# team13_4.net
KiCad netlist of a schematic drawn in EAGLE
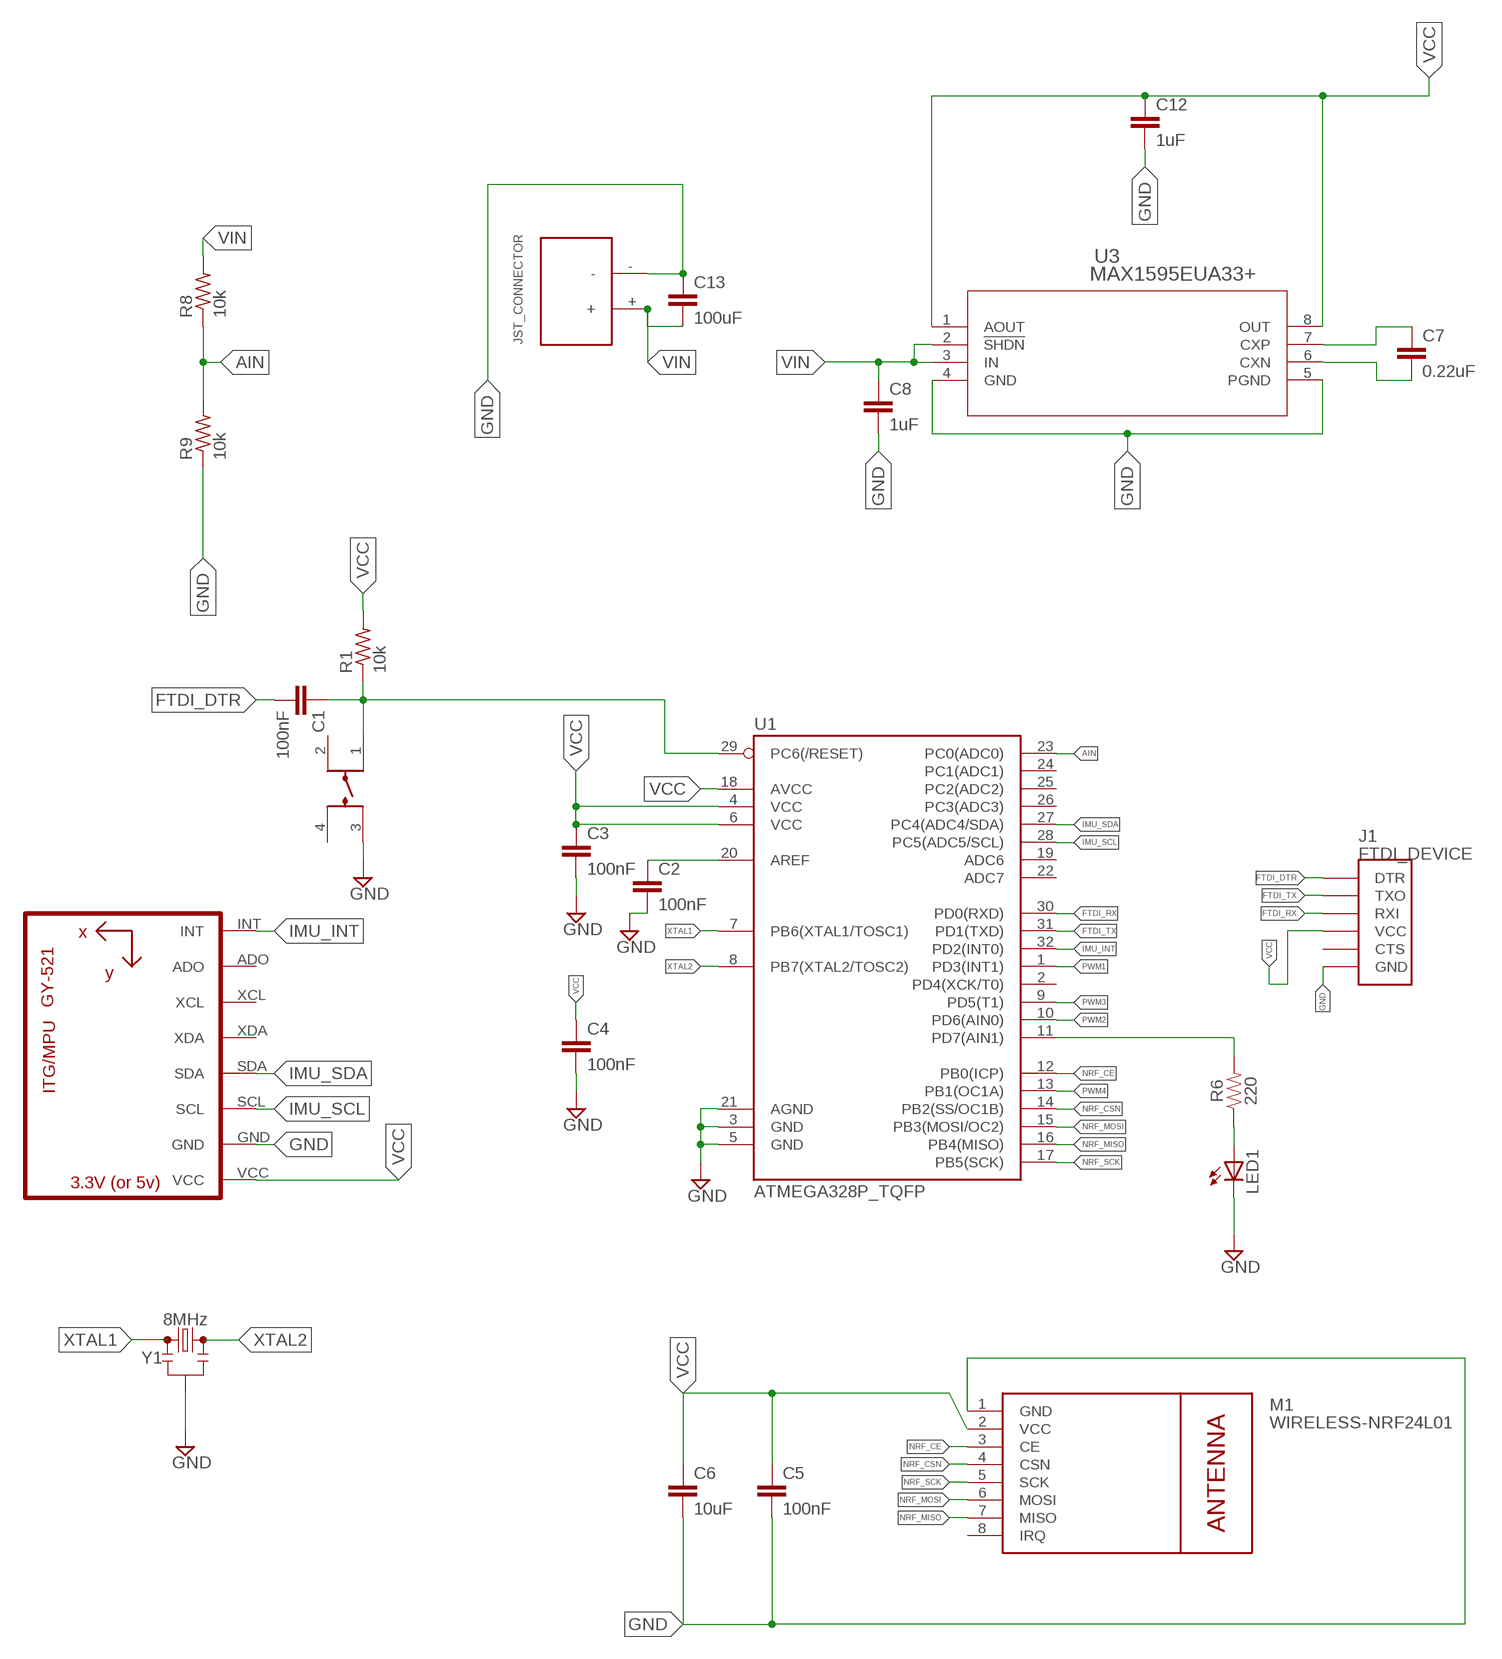
[diagram p0: schematic, sheet 1, part 1 of 3]
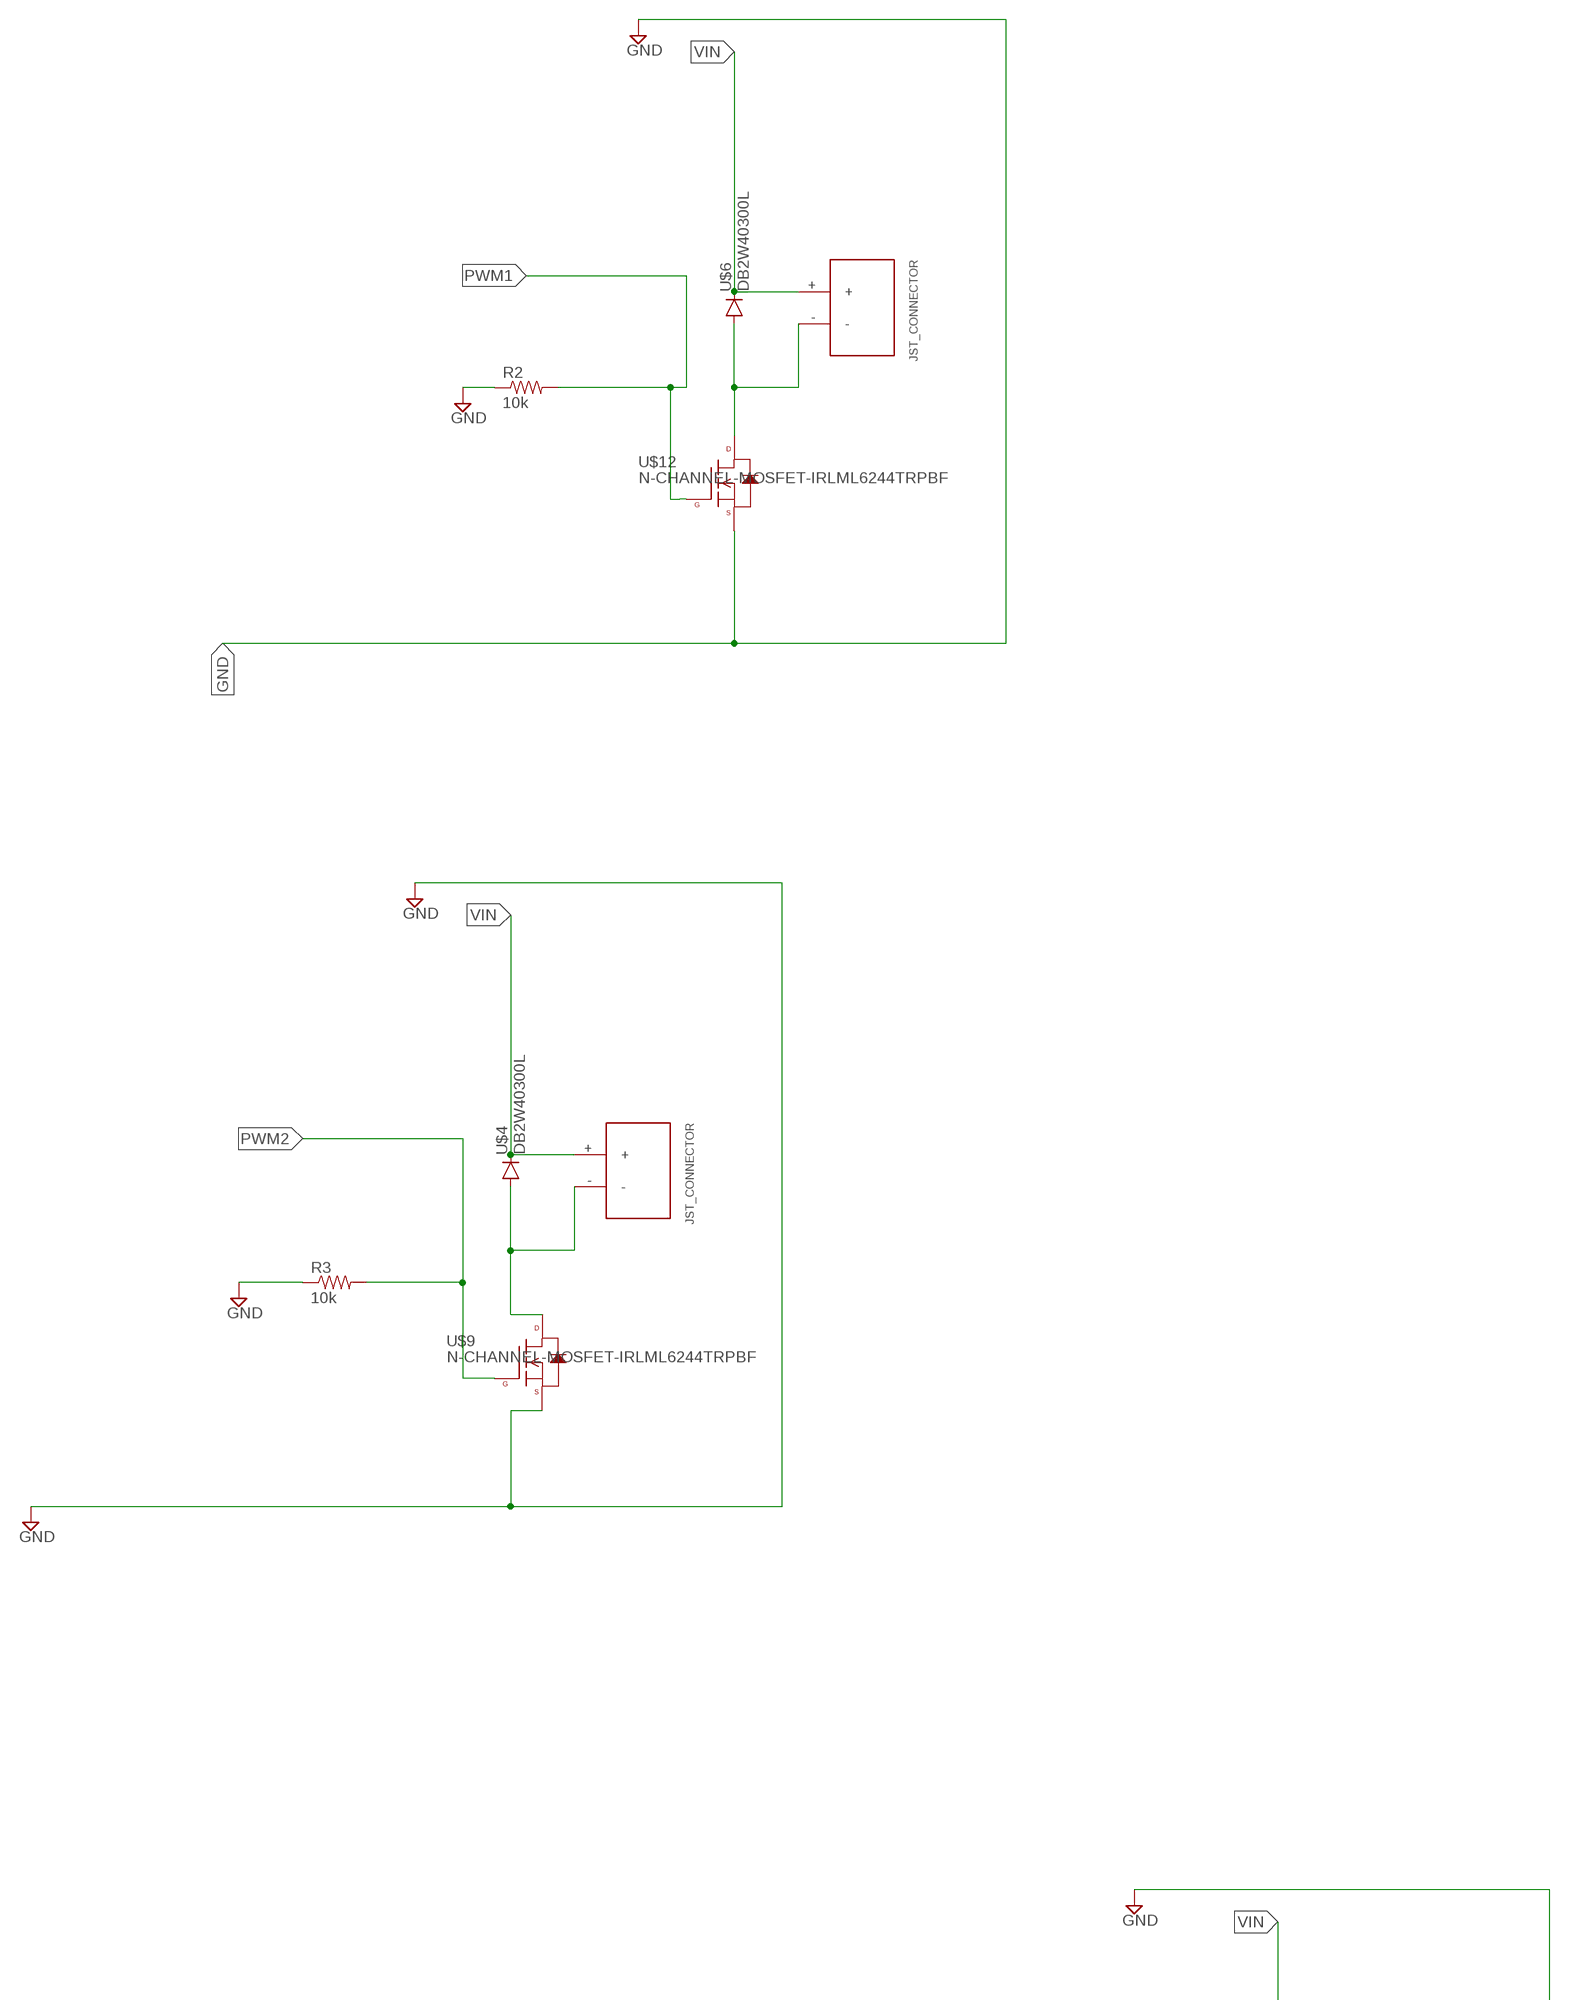
[diagram p1: schematic, sheet 1, part 2 of 3]
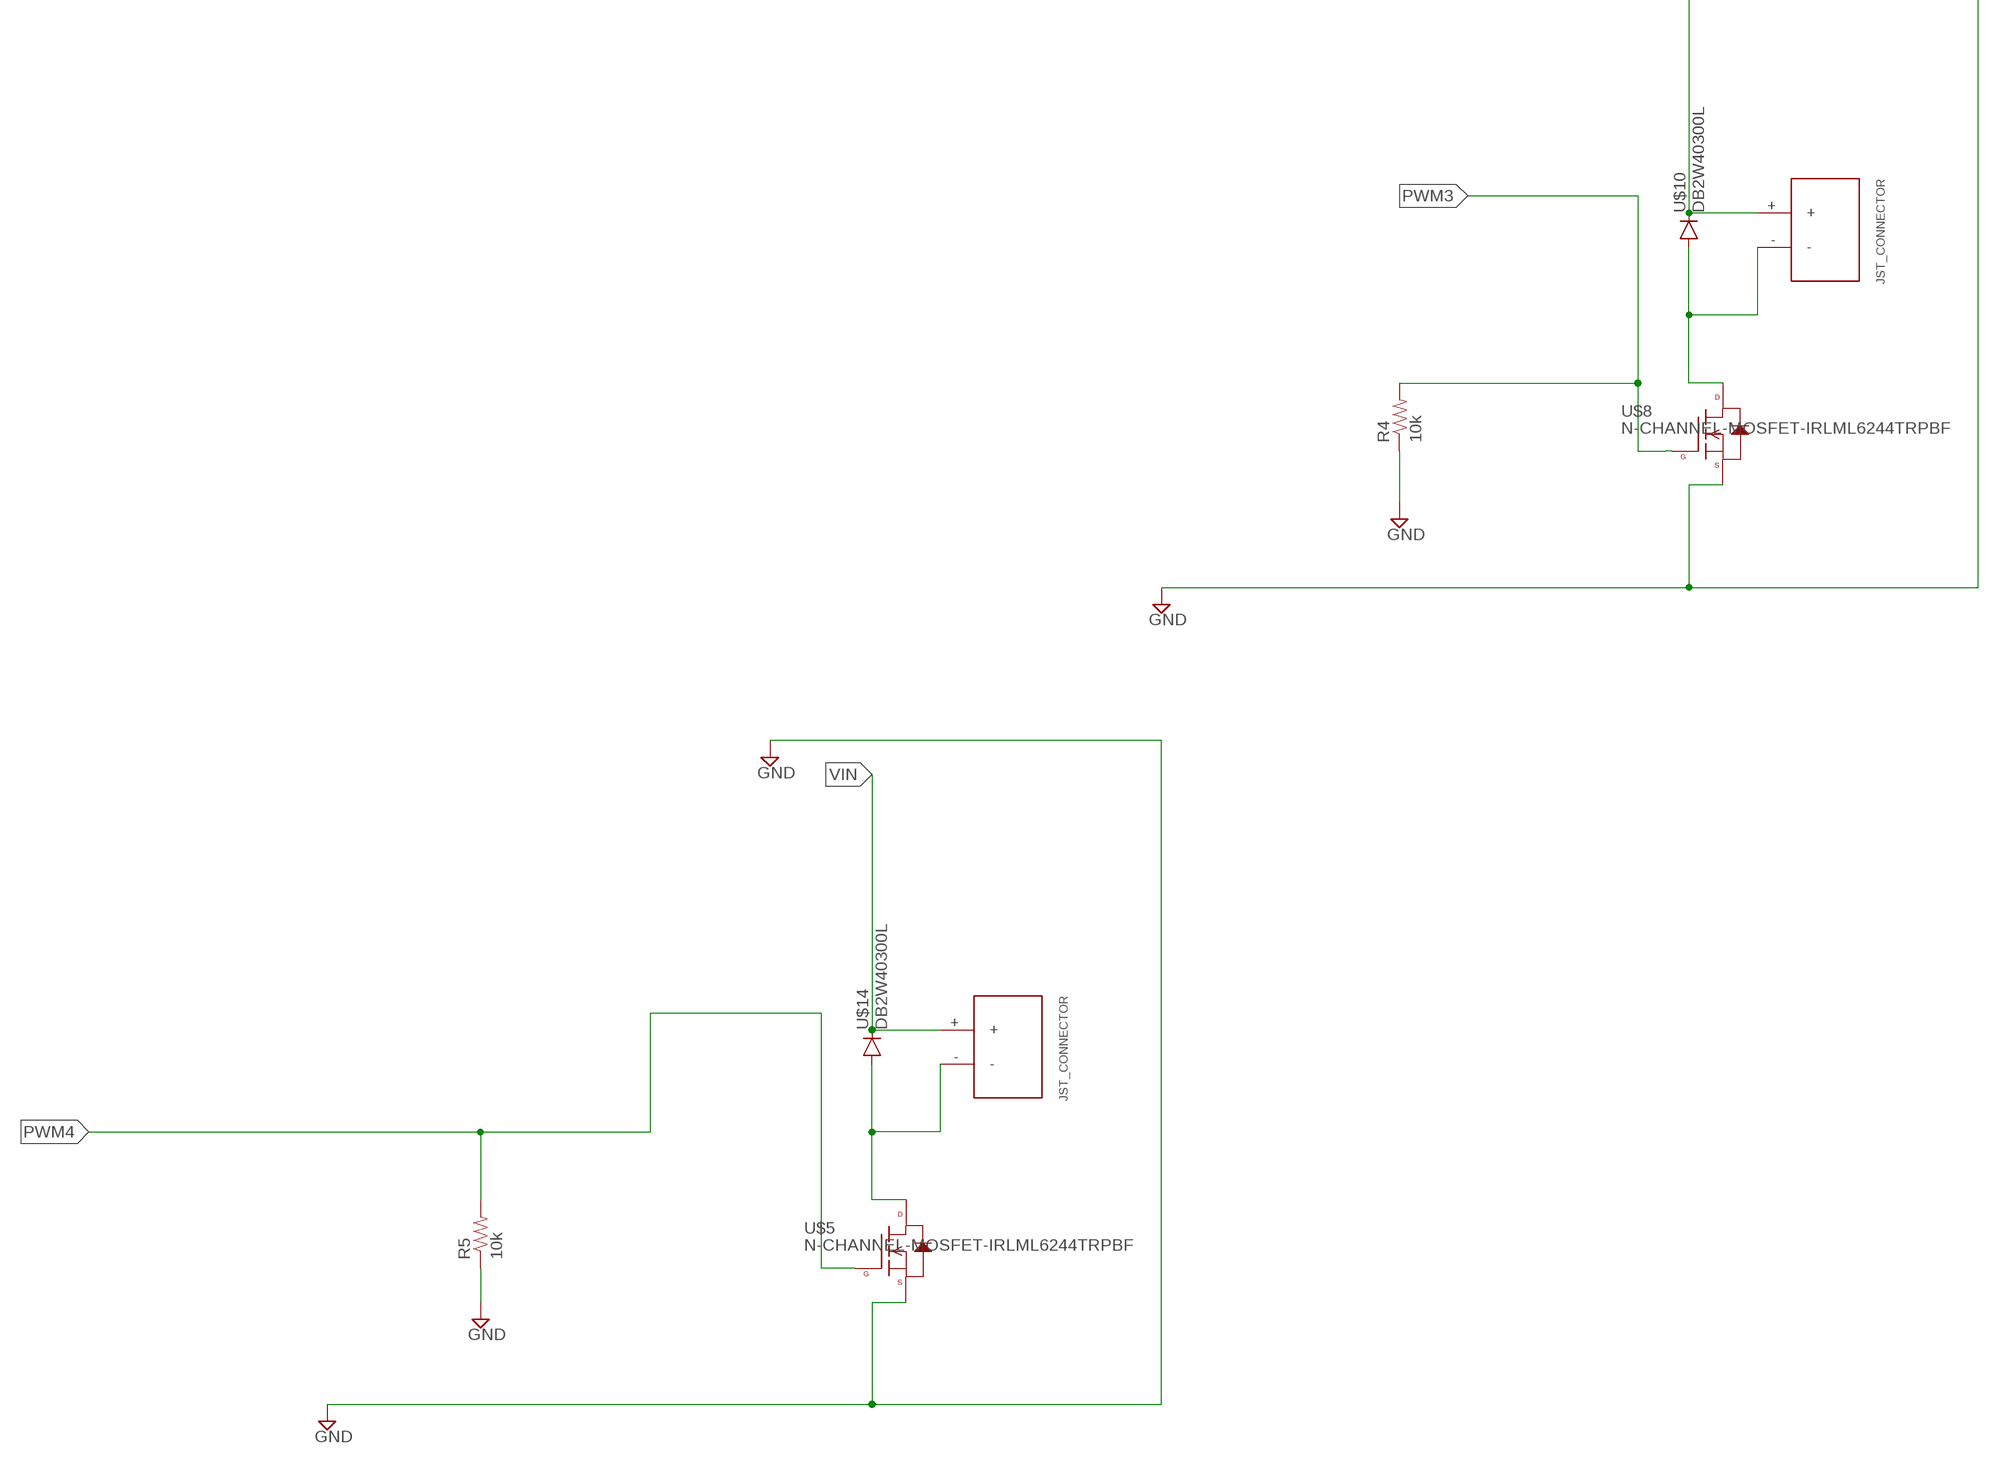
[diagram p2: schematic, sheet 1, part 3 of 3]

(export (version "E")
  (design (tool "Eeschema 10.0.6"))
  (components
    (comp (ref "C1")
      (value "100nF")
      (footprint "eagle-import:C0603")
      (libsource (lib "eagle-import") (part "C-EUC0603"))
    )
    (comp (ref "C2")
      (value "100nF")
      (footprint "eagle-import:C0603")
      (libsource (lib "eagle-import") (part "C-EUC0603"))
    )
    (comp (ref "C3")
      (value "100nF")
      (footprint "eagle-import:C0603")
      (libsource (lib "eagle-import") (part "C-EUC0603"))
    )
    (comp (ref "C4")
      (value "100nF")
      (footprint "eagle-import:C0603")
      (libsource (lib "eagle-import") (part "C-EUC0603"))
    )
    (comp (ref "C5")
      (value "100nF")
      (footprint "eagle-import:C0603")
      (libsource (lib "eagle-import") (part "C-EUC0603"))
    )
    (comp (ref "C6")
      (value "10uF")
      (footprint "eagle-import:C0603")
      (libsource (lib "eagle-import") (part "C-EUC0603"))
    )
    (comp (ref "C7")
      (value "0.22uF")
      (footprint "eagle-import:C0603")
      (libsource (lib "eagle-import") (part "C-EUC0603"))
    )
    (comp (ref "C8")
      (value "1uF")
      (footprint "eagle-import:C0805")
      (libsource (lib "eagle-import") (part "C-EUC0805"))
    )
    (comp (ref "C12")
      (value "1uF")
      (footprint "eagle-import:C0805")
      (libsource (lib "eagle-import") (part "C-EUC0805"))
    )
    (comp (ref "C13")
      (value "100uF")
      (footprint "eagle-import:C1210")
      (libsource (lib "eagle-import") (part "C-EUC1210"))
    )
    (comp (ref "J1")
      (value "FTDI_DEVICE")
      (footprint "eagle-import:FTDI_DEVICE_SIDE")
      (libsource (lib "eagle-import") (part "FTDI_DEVICE"))
    )
    (comp (ref "LED1")
      (value "LED1206")
      (footprint "eagle-import:LED-1206")
      (libsource (lib "eagle-import") (part "LED1206"))
    )
    (comp (ref "M1")
      (value "WIRELESS-NRF24L01")
      (footprint "eagle-import:WIRELESS-NRF24L01")
      (libsource (lib "eagle-import") (part "WIRELESS-NRF24L01"))
    )
    (comp (ref "R1")
      (value "10k")
      (footprint "eagle-import:R0603")
      (libsource (lib "eagle-import") (part "R-US_R0603"))
    )
    (comp (ref "R2")
      (value "10k")
      (footprint "eagle-import:0603-RES")
      (libsource (lib "eagle-import") (part "RESISTOR0603"))
    )
    (comp (ref "R3")
      (value "10k")
      (footprint "eagle-import:0603-RES")
      (libsource (lib "eagle-import") (part "RESISTOR0603"))
    )
    (comp (ref "R4")
      (value "10k")
      (footprint "eagle-import:0603-RES")
      (libsource (lib "eagle-import") (part "RESISTOR0603"))
    )
    (comp (ref "R5")
      (value "10k")
      (footprint "eagle-import:0603-RES")
      (libsource (lib "eagle-import") (part "RESISTOR0603"))
    )
    (comp (ref "R6")
      (value "220")
      (footprint "eagle-import:0603")
      (libsource (lib "eagle-import") (part "220OHM-0603-1/10W-1%"))
    )
    (comp (ref "R8")
      (value "10k")
      (footprint "eagle-import:R0603")
      (libsource (lib "eagle-import") (part "R-US_R0603"))
    )
    (comp (ref "R9")
      (value "10k")
      (footprint "eagle-import:R0603")
      (libsource (lib "eagle-import") (part "R-US_R0603"))
    )
    (comp (ref "U$1")
      (value "LL3301NF065QG")
      (footprint "eagle-import:LL3301NF065QG")
      (libsource (lib "eagle-import") (part "LL3301NF065QG"))
    )
    (comp (ref "U$3")
      (value "JST_CONNECTOR_FEMALE")
      (footprint "eagle-import:JST_CONNECTOR_FEMALE")
      (libsource (lib "eagle-import") (part "JST_CONNECTOR_FEMALE"))
    )
    (comp (ref "U$4")
      (value "DB2W40300L")
      (footprint "eagle-import:MINI2-F3-B")
      (libsource (lib "eagle-import") (part "DB2W40300L"))
    )
    (comp (ref "U$5")
      (value "N-CHANNEL-MOSFET-IRLML6244TRPBF")
      (footprint "eagle-import:SOT23-3")
      (libsource (lib "eagle-import") (part "N-CHANNEL-MOSFET-IRLML6244TRPBF"))
    )
    (comp (ref "U$6")
      (value "DB2W40300L")
      (footprint "eagle-import:MINI2-F3-B")
      (libsource (lib "eagle-import") (part "DB2W40300L"))
    )
    (comp (ref "U$7")
      (value "JST_CONNECTOR_FEMALE")
      (footprint "eagle-import:JST_CONNECTOR_FEMALE")
      (libsource (lib "eagle-import") (part "JST_CONNECTOR_FEMALE"))
    )
    (comp (ref "U$8")
      (value "N-CHANNEL-MOSFET-IRLML6244TRPBF")
      (footprint "eagle-import:SOT23-3")
      (libsource (lib "eagle-import") (part "N-CHANNEL-MOSFET-IRLML6244TRPBF"))
    )
    (comp (ref "U$9")
      (value "N-CHANNEL-MOSFET-IRLML6244TRPBF")
      (footprint "eagle-import:SOT23-3")
      (libsource (lib "eagle-import") (part "N-CHANNEL-MOSFET-IRLML6244TRPBF"))
    )
    (comp (ref "U$10")
      (value "DB2W40300L")
      (footprint "eagle-import:MINI2-F3-B")
      (libsource (lib "eagle-import") (part "DB2W40300L"))
    )
    (comp (ref "U$11")
      (value "JST_CONNECTOR_FEMALE")
      (footprint "eagle-import:JST_CONNECTOR_FEMALE")
      (libsource (lib "eagle-import") (part "JST_CONNECTOR_FEMALE"))
    )
    (comp (ref "U$12")
      (value "N-CHANNEL-MOSFET-IRLML6244TRPBF")
      (footprint "eagle-import:SOT23-3")
      (libsource (lib "eagle-import") (part "N-CHANNEL-MOSFET-IRLML6244TRPBF"))
    )
    (comp (ref "U$14")
      (value "DB2W40300L")
      (footprint "eagle-import:MINI2-F3-B")
      (libsource (lib "eagle-import") (part "DB2W40300L"))
    )
    (comp (ref "U$15")
      (value "JST_CONNECTOR_FEMALE")
      (footprint "eagle-import:JST_CONNECTOR_FEMALE")
      (libsource (lib "eagle-import") (part "JST_CONNECTOR_FEMALE"))
    )
    (comp (ref "U$19")
      (value "JST_CONNECTOR_FEMALE")
      (footprint "eagle-import:JST_CONNECTOR_FEMALE")
      (libsource (lib "eagle-import") (part "JST_CONNECTOR_FEMALE"))
    )
    (comp (ref "U1")
      (value "ATMEGA328P_TQFP")
      (footprint "eagle-import:TQFP32-08")
      (libsource (lib "eagle-import") (part "ATMEGA328P_TQFP"))
    )
    (comp (ref "U2")
      (value "GY-521MPU6050")
      (footprint "eagle-import:GY-521")
      (libsource (lib "eagle-import") (part "GY-521MPU6050"))
    )
    (comp (ref "U3")
      (value "MAX1595EUA33+")
      (footprint "eagle-import:21-0036K")
      (libsource (lib "eagle-import") (part "MAX1595EUA33+"))
    )
    (comp (ref "Y1")
      (value "8MHz")
      (footprint "eagle-import:RESONATOR-SMD-3.2X1.3")
      (libsource (lib "eagle-import") (part "RESONATOR-8MHZSMD_3.2X1.3"))
    )
  )
  (nets
    (net (code "1") (name "AIN") (class "Default")
      (node (ref "R8") (pin "1") (pinfunction "1_1") (pintype "passive"))
      (node (ref "R9") (pin "2") (pinfunction "2_2") (pintype "passive"))
      (node (ref "U1") (pin "23") (pinfunction "PC0(ADC0)_23") (pintype "bidirectional"))
    )
    (net (code "2") (name "FTDI_DTR") (class "Default")
      (node (ref "C1") (pin "2") (pinfunction "2_2") (pintype "passive"))
      (node (ref "J1") (pin "P$1") (pinfunction "DTR_P$1") (pintype "bidirectional"))
    )
    (net (code "3") (name "FTDI_RX") (class "Default")
      (node (ref "J1") (pin "P$3") (pinfunction "RXI_P$3") (pintype "bidirectional"))
      (node (ref "U1") (pin "30") (pinfunction "PD0(RXD)_30") (pintype "bidirectional"))
    )
    (net (code "4") (name "FTDI_TX") (class "Default")
      (node (ref "J1") (pin "P$2") (pinfunction "TXO_P$2") (pintype "bidirectional"))
      (node (ref "U1") (pin "31") (pinfunction "PD1(TXD)_31") (pintype "bidirectional"))
    )
    (net (code "5") (name "GND") (class "Default")
      (node (ref "C12") (pin "2") (pinfunction "2_2") (pintype "passive"))
      (node (ref "C13") (pin "1") (pinfunction "1_1") (pintype "passive"))
      (node (ref "C2") (pin "2") (pinfunction "2_2") (pintype "passive"))
      (node (ref "C3") (pin "2") (pinfunction "2_2") (pintype "passive"))
      (node (ref "C4") (pin "2") (pinfunction "2_2") (pintype "passive"))
      (node (ref "C5") (pin "2") (pinfunction "2_2") (pintype "passive"))
      (node (ref "C6") (pin "2") (pinfunction "2_2") (pintype "passive"))
      (node (ref "C8") (pin "2") (pinfunction "2_2") (pintype "passive"))
      (node (ref "J1") (pin "P$6") (pinfunction "GND_P$6") (pintype "bidirectional"))
      (node (ref "LED1") (pin "C") (pinfunction "C_C") (pintype "passive"))
      (node (ref "M1") (pin "1") (pinfunction "GND_1") (pintype "power_in"))
      (node (ref "R2") (pin "1") (pinfunction "1_1") (pintype "passive"))
      (node (ref "R3") (pin "1") (pinfunction "1_1") (pintype "passive"))
      (node (ref "R4") (pin "1") (pinfunction "1_1") (pintype "passive"))
      (node (ref "R5") (pin "1") (pinfunction "1_1") (pintype "passive"))
      (node (ref "R9") (pin "1") (pinfunction "1_1") (pintype "passive"))
      (node (ref "U$1") (pin "3") (pinfunction "3_3") (pintype "passive"))
      (node (ref "U$12") (pin "2") (pinfunction "S_2") (pintype "passive"))
      (node (ref "U$19") (pin "-") (pinfunction "-_-") (pintype "bidirectional"))
      (node (ref "U$5") (pin "2") (pinfunction "S_2") (pintype "passive"))
      (node (ref "U$8") (pin "2") (pinfunction "S_2") (pintype "passive"))
      (node (ref "U$9") (pin "2") (pinfunction "S_2") (pintype "passive"))
      (node (ref "U1") (pin "21") (pinfunction "AGND_21") (pintype "bidirectional"))
      (node (ref "U1") (pin "3") (pinfunction "GND_3") (pintype "bidirectional"))
      (node (ref "U1") (pin "5") (pinfunction "GND_5") (pintype "bidirectional"))
      (node (ref "U2") (pin "GND") (pinfunction "GND_GND") (pintype "bidirectional"))
      (node (ref "U3") (pin "4") (pinfunction "GND_4") (pintype "power_in"))
      (node (ref "U3") (pin "5") (pinfunction "PGND_5") (pintype "passive"))
      (node (ref "Y1") (pin "2") (pinfunction "2_2") (pintype "passive"))
    )
    (net (code "6") (name "IMU_INT") (class "Default")
      (node (ref "U1") (pin "32") (pinfunction "PD2(INT0)_32") (pintype "bidirectional"))
      (node (ref "U2") (pin "INT") (pinfunction "INT_INT") (pintype "bidirectional"))
    )
    (net (code "7") (name "IMU_SCL") (class "Default")
      (node (ref "U1") (pin "28") (pinfunction "PC5(ADC5/SCL)_28") (pintype "bidirectional"))
      (node (ref "U2") (pin "SCL") (pinfunction "SCL_SCL") (pintype "bidirectional"))
    )
    (net (code "8") (name "IMU_SDA") (class "Default")
      (node (ref "U1") (pin "27") (pinfunction "PC4(ADC4/SDA)_27") (pintype "bidirectional"))
      (node (ref "U2") (pin "SDA") (pinfunction "SDA_SDA") (pintype "bidirectional"))
    )
    (net (code "9") (name "NRF_CE") (class "Default")
      (node (ref "M1") (pin "3") (pinfunction "CE_3") (pintype "bidirectional"))
      (node (ref "U1") (pin "12") (pinfunction "PB0(ICP)_12") (pintype "bidirectional"))
    )
    (net (code "10") (name "NRF_CSN") (class "Default")
      (node (ref "M1") (pin "4") (pinfunction "CSN_4") (pintype "bidirectional"))
      (node (ref "U1") (pin "14") (pinfunction "PB2(SS/OC1B)_14") (pintype "bidirectional"))
    )
    (net (code "11") (name "NRF_MISO") (class "Default")
      (node (ref "M1") (pin "7") (pinfunction "MISO_7") (pintype "bidirectional"))
      (node (ref "U1") (pin "16") (pinfunction "PB4(MISO)_16") (pintype "bidirectional"))
    )
    (net (code "12") (name "NRF_MOSI") (class "Default")
      (node (ref "M1") (pin "6") (pinfunction "MOSI_6") (pintype "bidirectional"))
      (node (ref "U1") (pin "15") (pinfunction "PB3(MOSI/OC2)_15") (pintype "bidirectional"))
    )
    (net (code "13") (name "NRF_SCK") (class "Default")
      (node (ref "M1") (pin "5") (pinfunction "SCK_5") (pintype "bidirectional"))
      (node (ref "U1") (pin "17") (pinfunction "PB5(SCK)_17") (pintype "bidirectional"))
    )
    (net (code "14") (name "Net-(LED1-PadA)") (class "Default")
      (node (ref "LED1") (pin "A") (pinfunction "A_A") (pintype "passive"))
      (node (ref "R6") (pin "1") (pinfunction "1_1") (pintype "passive"))
    )
    (net (code "15") (name "Net-(U$4-PPIN)") (class "Default")
      (node (ref "U$3") (pin "-") (pinfunction "-_-") (pintype "bidirectional"))
      (node (ref "U$4") (pin "POS") (pinfunction "PPIN_POS") (pintype "passive"))
      (node (ref "U$9") (pin "3") (pinfunction "D_3") (pintype "passive"))
    )
    (net (code "16") (name "Net-(U$10-PPIN)") (class "Default")
      (node (ref "U$10") (pin "POS") (pinfunction "PPIN_POS") (pintype "passive"))
      (node (ref "U$11") (pin "-") (pinfunction "-_-") (pintype "bidirectional"))
      (node (ref "U$8") (pin "3") (pinfunction "D_3") (pintype "passive"))
    )
    (net (code "17") (name "Net-(U$12-D)") (class "Default")
      (node (ref "U$12") (pin "3") (pinfunction "D_3") (pintype "passive"))
      (node (ref "U$6") (pin "POS") (pinfunction "PPIN_POS") (pintype "passive"))
      (node (ref "U$7") (pin "-") (pinfunction "-_-") (pintype "bidirectional"))
    )
    (net (code "18") (name "Net-(U$14-PPIN)") (class "Default")
      (node (ref "U$14") (pin "POS") (pinfunction "PPIN_POS") (pintype "passive"))
      (node (ref "U$15") (pin "-") (pinfunction "-_-") (pintype "bidirectional"))
      (node (ref "U$5") (pin "3") (pinfunction "D_3") (pintype "passive"))
    )
    (net (code "19") (name "Net-(U1-AREF)") (class "Default")
      (node (ref "C2") (pin "1") (pinfunction "1_1") (pintype "passive"))
      (node (ref "U1") (pin "20") (pinfunction "AREF_20") (pintype "bidirectional"))
    )
    (net (code "20") (name "Net-(U1-PC6({slash}RESET))") (class "Default")
      (node (ref "C1") (pin "1") (pinfunction "1_1") (pintype "passive"))
      (node (ref "R1") (pin "1") (pinfunction "1_1") (pintype "passive"))
      (node (ref "U$1") (pin "1") (pinfunction "1_1") (pintype "passive"))
      (node (ref "U1") (pin "29") (pinfunction "PC6(/RESET)_29") (pintype "bidirectional"))
    )
    (net (code "21") (name "Net-(U1-PD7(AIN1))") (class "Default")
      (node (ref "R6") (pin "2") (pinfunction "2_2") (pintype "passive"))
      (node (ref "U1") (pin "11") (pinfunction "PD7(AIN1)_11") (pintype "bidirectional"))
    )
    (net (code "22") (name "Net-(U3-CXN)") (class "Default")
      (node (ref "C7") (pin "2") (pinfunction "2_2") (pintype "passive"))
      (node (ref "U3") (pin "6") (pinfunction "CXN_6") (pintype "passive"))
    )
    (net (code "23") (name "Net-(U3-CXP)") (class "Default")
      (node (ref "C7") (pin "1") (pinfunction "1_1") (pintype "passive"))
      (node (ref "U3") (pin "7") (pinfunction "CXP_7") (pintype "passive"))
    )
    (net (code "24") (name "PWM1") (class "Default")
      (node (ref "R2") (pin "2") (pinfunction "2_2") (pintype "passive"))
      (node (ref "U$12") (pin "1") (pinfunction "G_1") (pintype "passive"))
      (node (ref "U1") (pin "1") (pinfunction "PD3(INT1)_1") (pintype "bidirectional"))
    )
    (net (code "25") (name "PWM2") (class "Default")
      (node (ref "R3") (pin "2") (pinfunction "2_2") (pintype "passive"))
      (node (ref "U$9") (pin "1") (pinfunction "G_1") (pintype "passive"))
      (node (ref "U1") (pin "10") (pinfunction "PD6(AIN0)_10") (pintype "bidirectional"))
    )
    (net (code "26") (name "PWM3") (class "Default")
      (node (ref "R4") (pin "2") (pinfunction "2_2") (pintype "passive"))
      (node (ref "U$8") (pin "1") (pinfunction "G_1") (pintype "passive"))
      (node (ref "U1") (pin "9") (pinfunction "PD5(T1)_9") (pintype "bidirectional"))
    )
    (net (code "27") (name "PWM4") (class "Default")
      (node (ref "R5") (pin "2") (pinfunction "2_2") (pintype "passive"))
      (node (ref "U$5") (pin "1") (pinfunction "G_1") (pintype "passive"))
      (node (ref "U1") (pin "13") (pinfunction "PB1(OC1A)_13") (pintype "bidirectional"))
    )
    (net (code "28") (name "VCC") (class "Default")
      (node (ref "C12") (pin "1") (pinfunction "1_1") (pintype "passive"))
      (node (ref "C3") (pin "1") (pinfunction "1_1") (pintype "passive"))
      (node (ref "C4") (pin "1") (pinfunction "1_1") (pintype "passive"))
      (node (ref "C5") (pin "1") (pinfunction "1_1") (pintype "passive"))
      (node (ref "C6") (pin "1") (pinfunction "1_1") (pintype "passive"))
      (node (ref "J1") (pin "P$4") (pinfunction "VCC_P$4") (pintype "bidirectional"))
      (node (ref "M1") (pin "2") (pinfunction "VCC_2") (pintype "power_in"))
      (node (ref "R1") (pin "2") (pinfunction "2_2") (pintype "passive"))
      (node (ref "U1") (pin "18") (pinfunction "AVCC_18") (pintype "bidirectional"))
      (node (ref "U1") (pin "4") (pinfunction "VCC_4") (pintype "bidirectional"))
      (node (ref "U1") (pin "6") (pinfunction "VCC_6") (pintype "bidirectional"))
      (node (ref "U2") (pin "VCC") (pinfunction "VCC_VCC") (pintype "bidirectional"))
      (node (ref "U3") (pin "1") (pinfunction "AOUT_1") (pintype "passive"))
      (node (ref "U3") (pin "8") (pinfunction "OUT_8") (pintype "passive"))
    )
    (net (code "29") (name "VIN") (class "Default")
      (node (ref "C13") (pin "2") (pinfunction "2_2") (pintype "passive"))
      (node (ref "C8") (pin "1") (pinfunction "1_1") (pintype "passive"))
      (node (ref "R8") (pin "2") (pinfunction "2_2") (pintype "passive"))
      (node (ref "U$10") (pin "NEG") (pinfunction "GPIN_NEG") (pintype "passive"))
      (node (ref "U$11") (pin "+") (pinfunction "+_+") (pintype "bidirectional"))
      (node (ref "U$14") (pin "NEG") (pinfunction "GPIN_NEG") (pintype "passive"))
      (node (ref "U$15") (pin "+") (pinfunction "+_+") (pintype "bidirectional"))
      (node (ref "U$19") (pin "+") (pinfunction "+_+") (pintype "bidirectional"))
      (node (ref "U$3") (pin "+") (pinfunction "+_+") (pintype "bidirectional"))
      (node (ref "U$4") (pin "NEG") (pinfunction "GPIN_NEG") (pintype "passive"))
      (node (ref "U$6") (pin "NEG") (pinfunction "GPIN_NEG") (pintype "passive"))
      (node (ref "U$7") (pin "+") (pinfunction "+_+") (pintype "bidirectional"))
      (node (ref "U3") (pin "2") (pinfunction "~{SHDN}_2") (pintype "passive"))
      (node (ref "U3") (pin "3") (pinfunction "IN_3") (pintype "input"))
    )
    (net (code "30") (name "XTAL1") (class "Default")
      (node (ref "U1") (pin "7") (pinfunction "PB6(XTAL1/TOSC1)_7") (pintype "bidirectional"))
      (node (ref "Y1") (pin "1") (pinfunction "1_1") (pintype "passive"))
    )
    (net (code "31") (name "XTAL2") (class "Default")
      (node (ref "U1") (pin "8") (pinfunction "PB7(XTAL2/TOSC2)_8") (pintype "bidirectional"))
      (node (ref "Y1") (pin "3") (pinfunction "3_3") (pintype "passive"))
    )
    (net (code "32") (name "unconnected-(J1-CTS-PadP$5)") (class "Default")
      (node (ref "J1") (pin "P$5") (pinfunction "CTS_P$5") (pintype "bidirectional"))
    )
    (net (code "33") (name "unconnected-(M1-IRQ-Pad8)") (class "Default")
      (node (ref "M1") (pin "8") (pinfunction "IRQ_8") (pintype "bidirectional"))
    )
    (net (code "34") (name "unconnected-(U$1-Pad2)") (class "Default")
      (node (ref "U$1") (pin "2") (pinfunction "2_2") (pintype "passive"))
    )
    (net (code "35") (name "unconnected-(U$1-Pad4)") (class "Default")
      (node (ref "U$1") (pin "4") (pinfunction "4_4") (pintype "passive"))
    )
    (net (code "36") (name "unconnected-(U1-ADC6-Pad19)") (class "Default")
      (node (ref "U1") (pin "19") (pinfunction "ADC6_19") (pintype "bidirectional"))
    )
    (net (code "37") (name "unconnected-(U1-ADC7-Pad22)") (class "Default")
      (node (ref "U1") (pin "22") (pinfunction "ADC7_22") (pintype "bidirectional"))
    )
    (net (code "38") (name "unconnected-(U1-PC1(ADC1)-Pad24)") (class "Default")
      (node (ref "U1") (pin "24") (pinfunction "PC1(ADC1)_24") (pintype "bidirectional"))
    )
    (net (code "39") (name "unconnected-(U1-PC2(ADC2)-Pad25)") (class "Default")
      (node (ref "U1") (pin "25") (pinfunction "PC2(ADC2)_25") (pintype "bidirectional"))
    )
    (net (code "40") (name "unconnected-(U1-PC3(ADC3)-Pad26)") (class "Default")
      (node (ref "U1") (pin "26") (pinfunction "PC3(ADC3)_26") (pintype "bidirectional"))
    )
    (net (code "41") (name "unconnected-(U1-PD4(XCK{slash}T0)-Pad2)") (class "Default")
      (node (ref "U1") (pin "2") (pinfunction "PD4(XCK/T0)_2") (pintype "bidirectional"))
    )
    (net (code "42") (name "unconnected-(U2-PadADO)") (class "Default")
      (node (ref "U2") (pin "ADO") (pinfunction "ADO_ADO") (pintype "bidirectional"))
    )
    (net (code "43") (name "unconnected-(U2-PadXCL)") (class "Default")
      (node (ref "U2") (pin "XCL") (pinfunction "XCL_XCL") (pintype "bidirectional"))
    )
    (net (code "44") (name "unconnected-(U2-PadXDA)") (class "Default")
      (node (ref "U2") (pin "XDA") (pinfunction "XDA_XDA") (pintype "bidirectional"))
    )
  )
)
